# STM32F207VC_Mini.net
KiCad netlist of a schematic drawn in Altium Designer
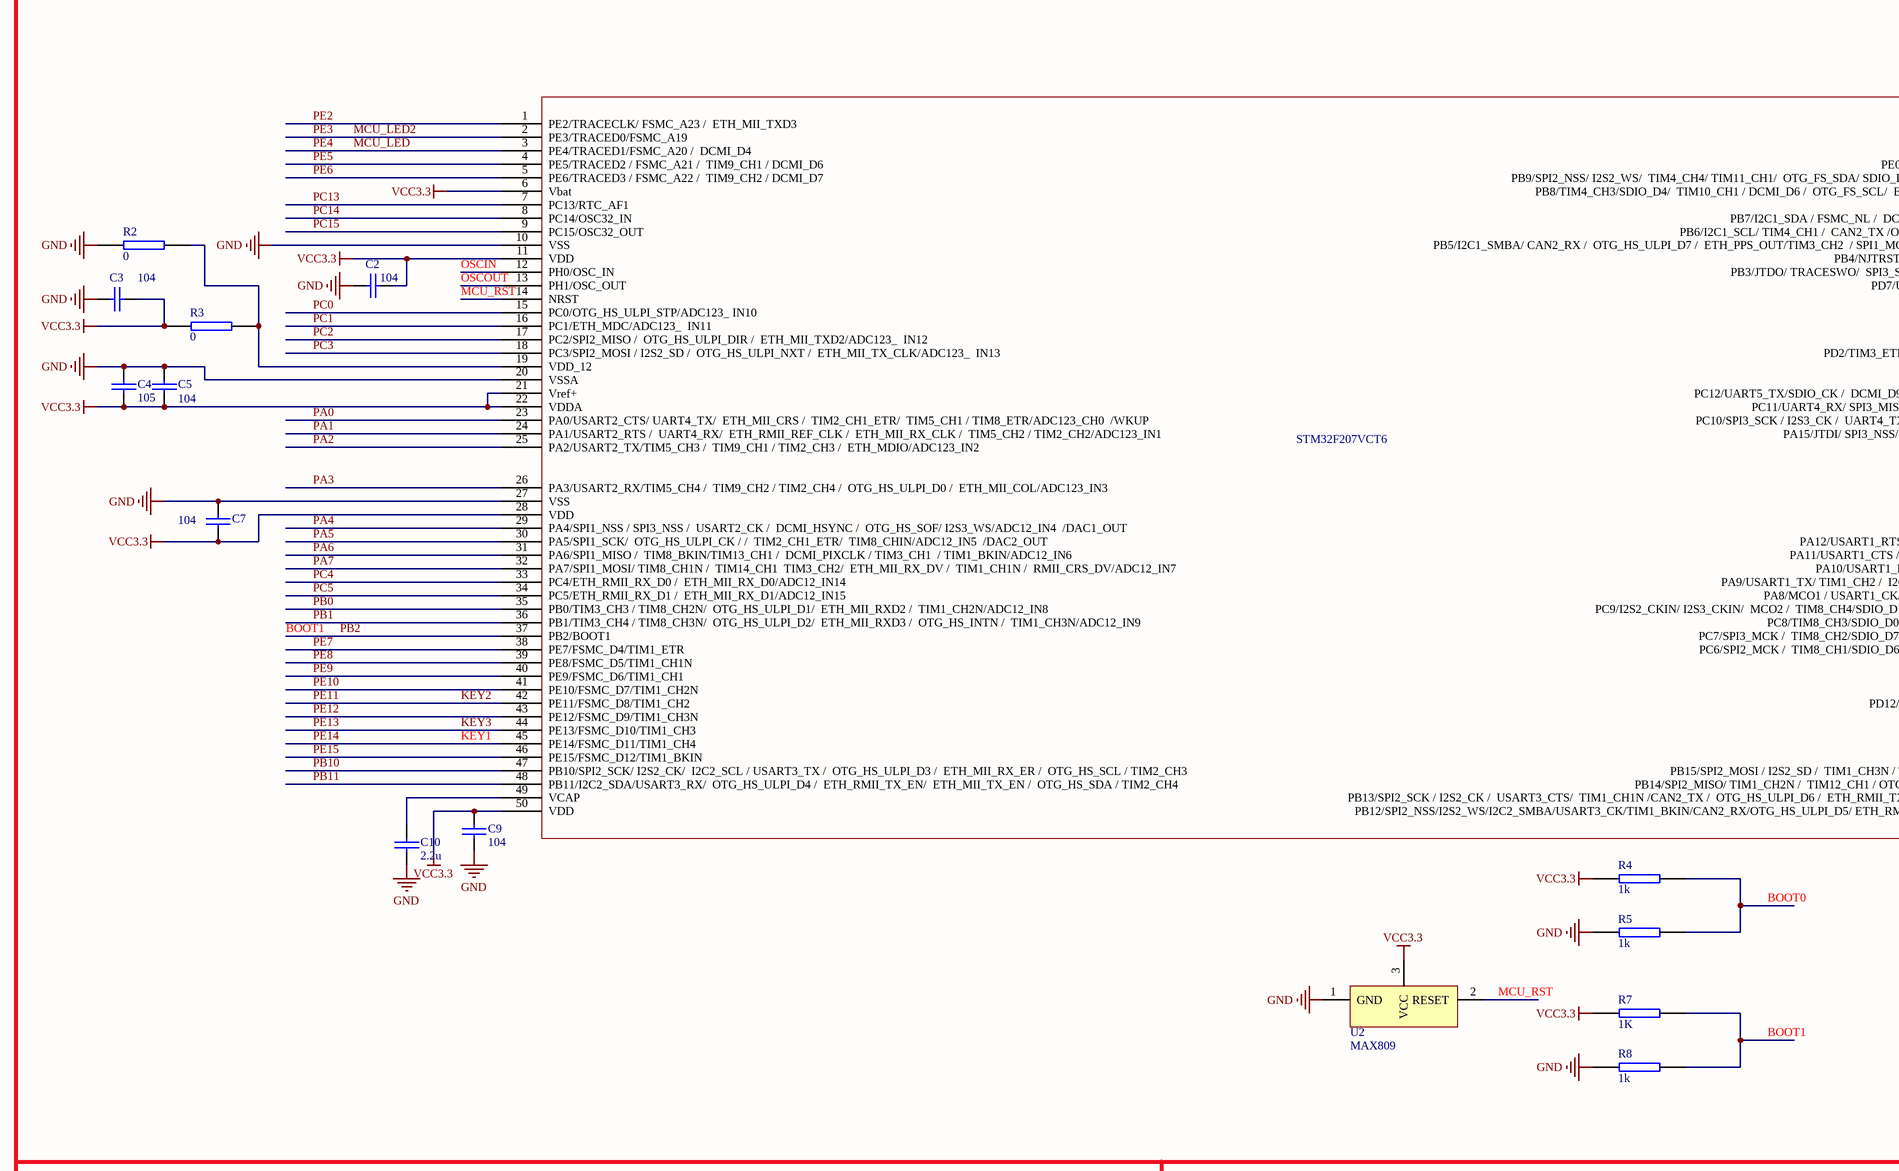
[diagram p0: STM32F207VC_Mini.SchDoc, top left]
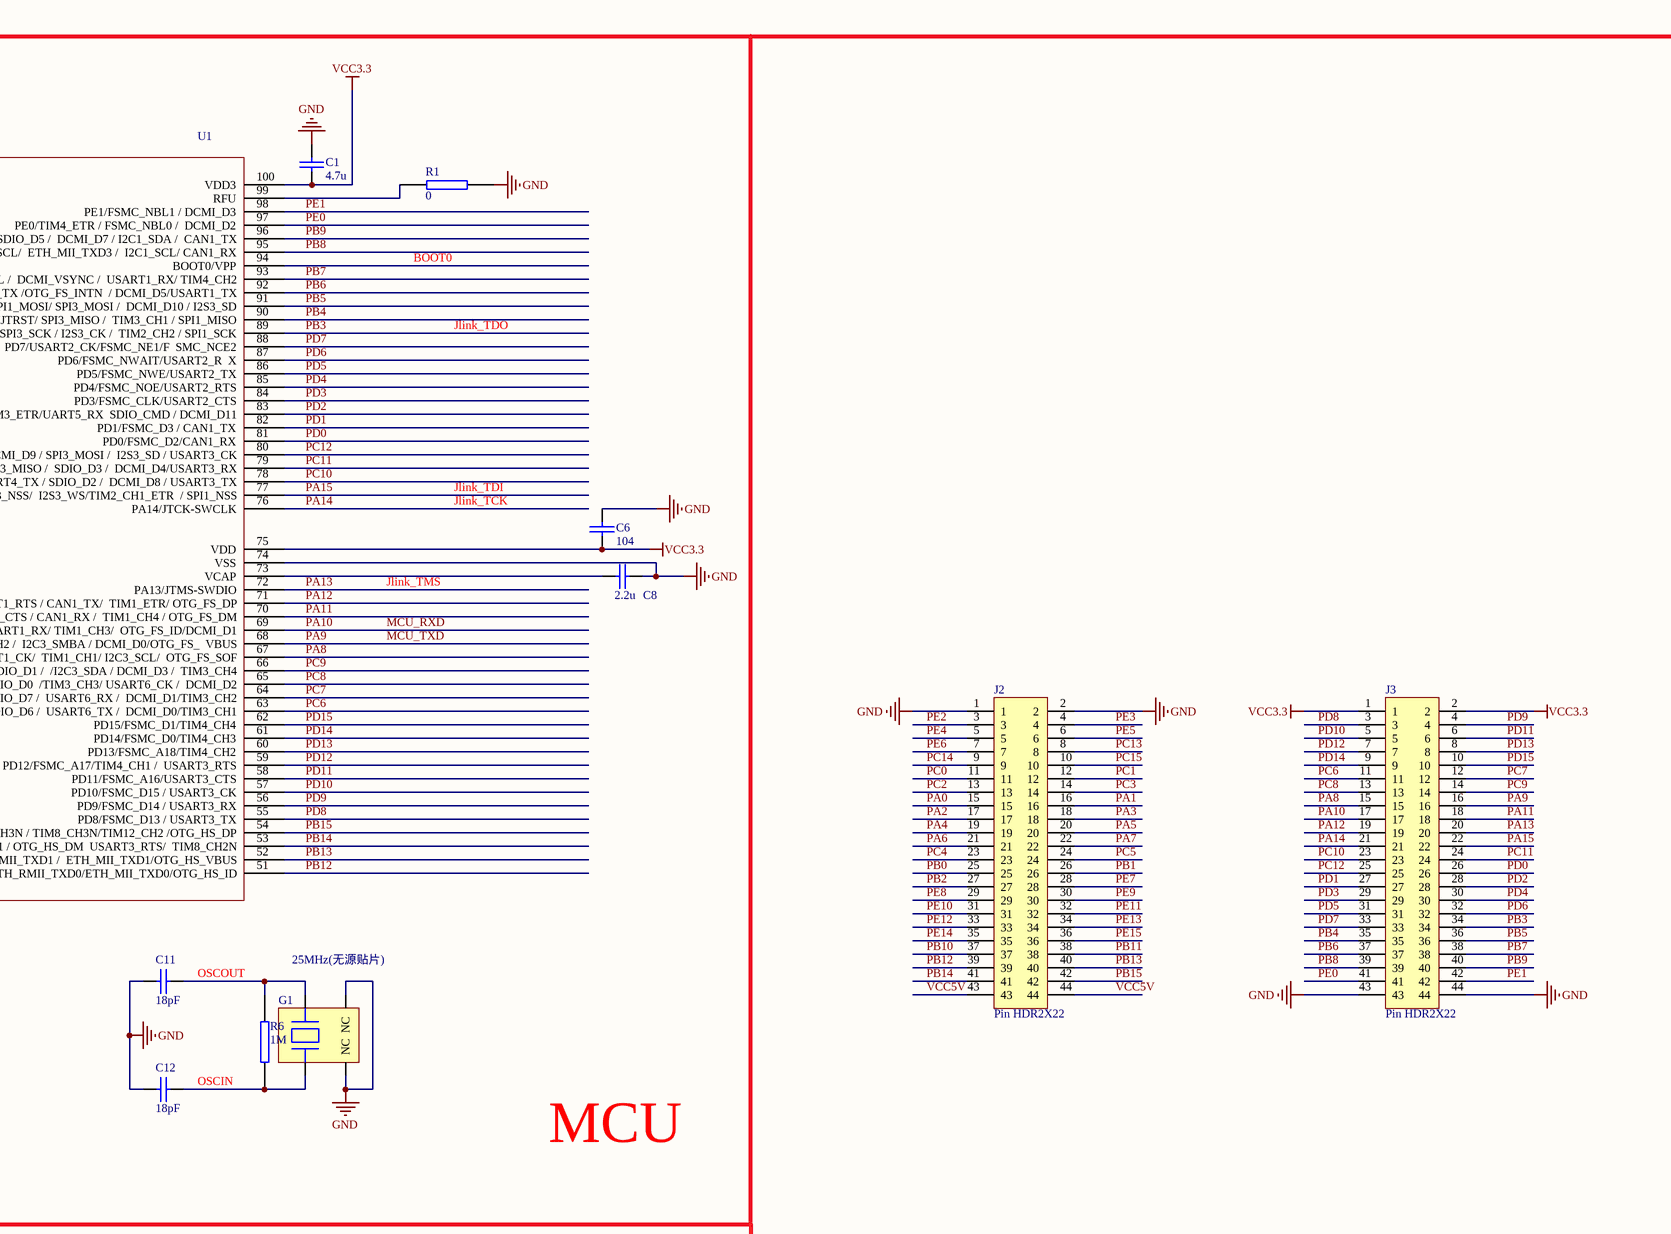
[diagram p1: STM32F207VC_Mini.SchDoc, top middle]
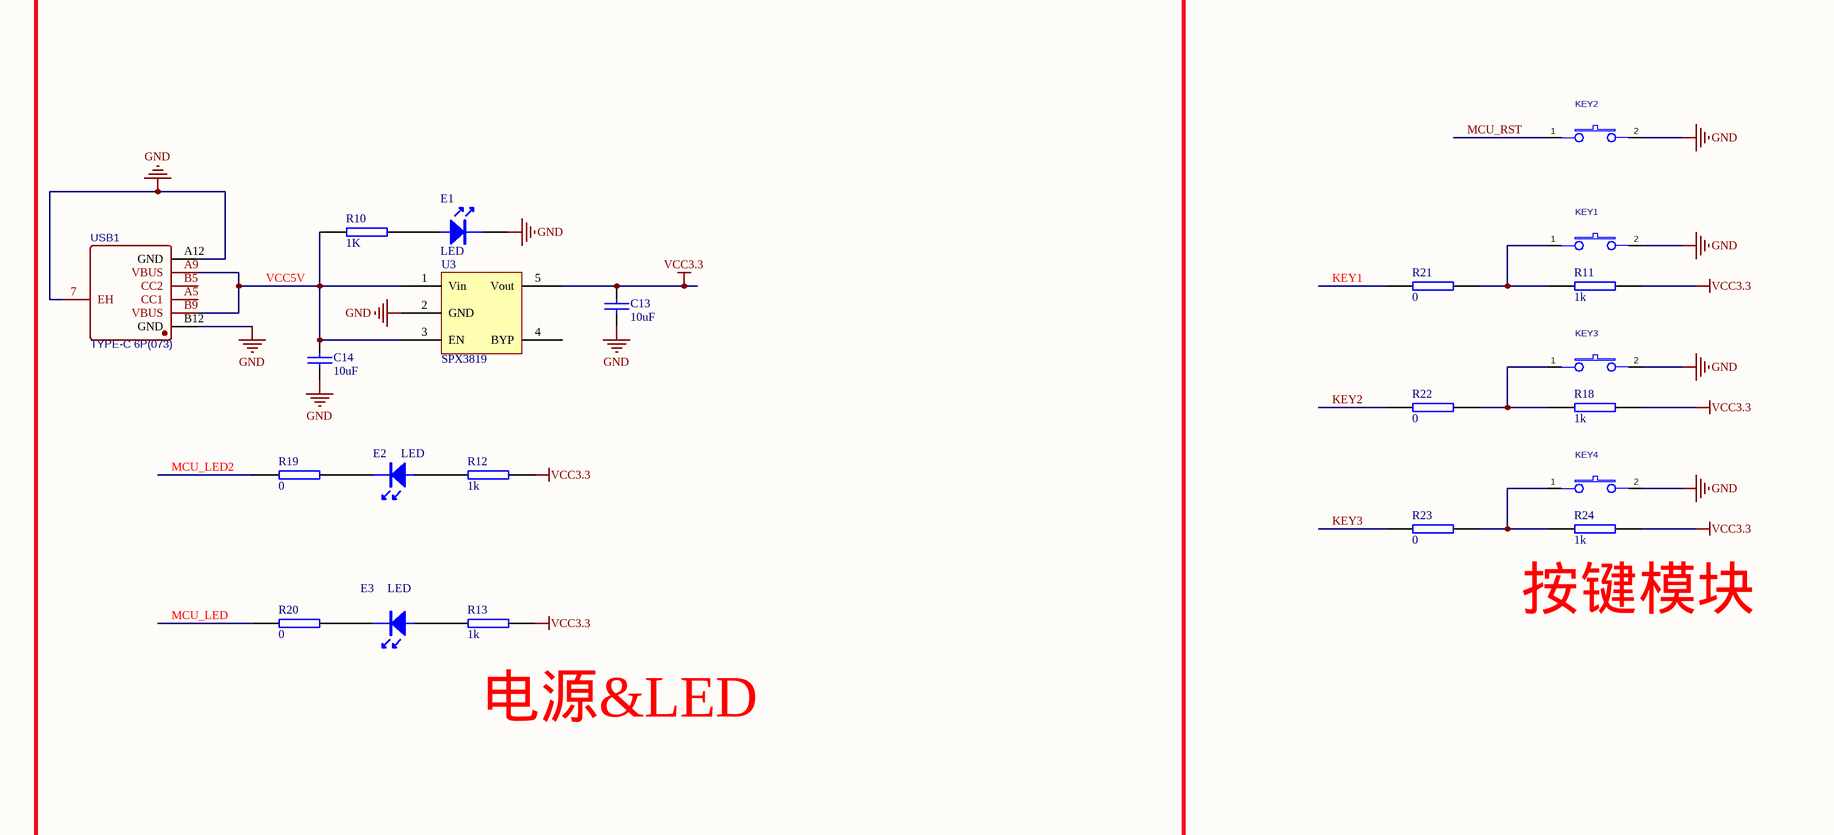
[diagram p2: STM32F207VC_Mini.SchDoc, bottom left]
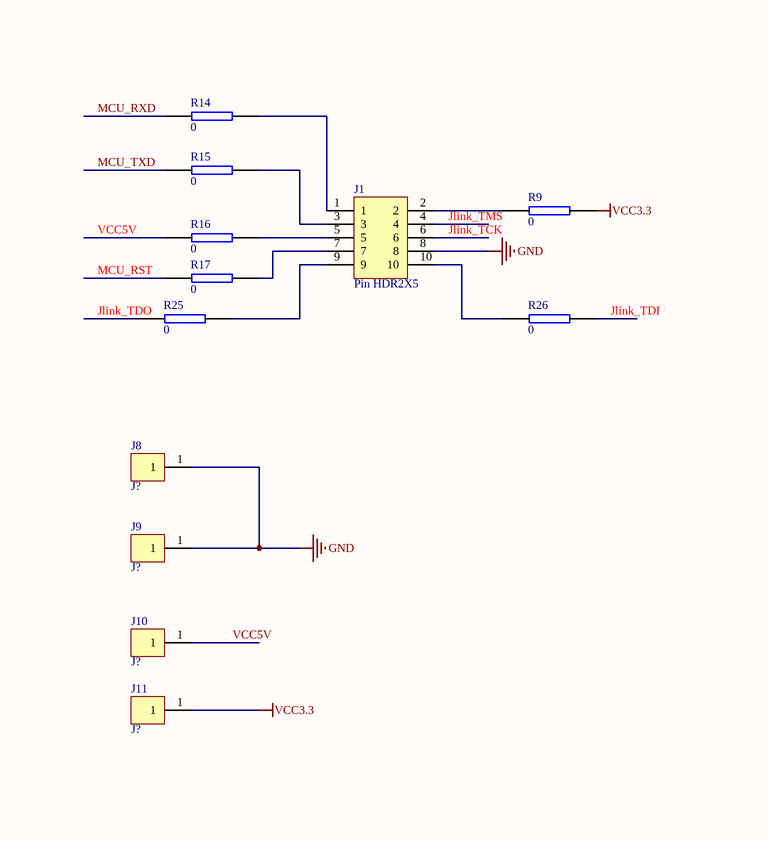
[diagram p3: STM32F207VC_Mini.SchDoc, bottom middle]

(export (version "E")
  (design (tool "Eeschema 10.0.6"))
  (components
    (comp (ref "C1")
      (value "4.7u")
      (footprint "0603")
      (description "贴片电容")
      (libsource (lib "ZXBC") (part "CAP Nonpolarity"))
    )
    (comp (ref "C2")
      (value "104")
      (footprint "0603")
      (description "贴片电容")
      (libsource (lib "ZXBC") (part "CAP Nonpolarity"))
    )
    (comp (ref "C3")
      (value "104")
      (footprint "0603")
      (description "贴片电容")
      (libsource (lib "ZXBC") (part "CAP Nonpolarity"))
    )
    (comp (ref "C4")
      (value "105")
      (footprint "0603")
      (description "贴片电容")
      (libsource (lib "ZXBC") (part "CAP Nonpolarity"))
    )
    (comp (ref "C5")
      (value "104")
      (footprint "0603")
      (description "贴片电容")
      (libsource (lib "ZXBC") (part "CAP Nonpolarity"))
    )
    (comp (ref "C6")
      (value "104")
      (footprint "0603")
      (description "贴片电容")
      (libsource (lib "ZXBC") (part "CAP Nonpolarity"))
    )
    (comp (ref "C7")
      (value "104")
      (footprint "0603")
      (description "贴片电容")
      (libsource (lib "ZXBC") (part "CAP Nonpolarity"))
    )
    (comp (ref "C8")
      (value "2.2u")
      (footprint "0603")
      (description "贴片电容")
      (libsource (lib "ZXBC") (part "CAP Nonpolarity"))
    )
    (comp (ref "C9")
      (value "104")
      (footprint "0603")
      (description "贴片电容")
      (libsource (lib "ZXBC") (part "CAP Nonpolarity"))
    )
    (comp (ref "C10")
      (value "2.2u")
      (footprint "0603")
      (description "贴片电容")
      (libsource (lib "ZXBC") (part "CAP Nonpolarity"))
    )
    (comp (ref "C11")
      (value "18pF")
      (footprint "0603")
      (description "无极电容")
      (libsource (lib "ZXBC") (part "CAP Nonpolarity"))
    )
    (comp (ref "C12")
      (value "18pF")
      (footprint "0603")
      (description "无极电容")
      (libsource (lib "ZXBC") (part "CAP Nonpolarity"))
    )
    (comp (ref "C13")
      (value "10uF")
      (footprint "0603")
      (description "无极电容")
      (libsource (lib "ZXBC") (part "CAP Nonpolarity"))
    )
    (comp (ref "C14")
      (value "10uF")
      (footprint "0603")
      (description "无极电容")
      (libsource (lib "ZXBC") (part "CAP Nonpolarity"))
    )
    (comp (ref "E1")
      (value "LED")
      (footprint "LED_0603L")
      (description "LED灯")
      (libsource (lib "ZXBC") (part "LED"))
    )
    (comp (ref "E2")
      (value "LED")
      (footprint "LED_0603L")
      (description "LED灯")
      (libsource (lib "ZXBC") (part "LED"))
    )
    (comp (ref "E3")
      (value "LED")
      (footprint "LED_0603L")
      (description "LED灯")
      (libsource (lib "ZXBC") (part "LED"))
    )
    (comp (ref "G1")
      (value "25MHz(无源贴片)")
      (footprint "G3225")
      (description "无源晶振MCU使用")
      (libsource (lib "ZXBC") (part "MM-11B"))
    )
    (comp (ref "J1")
      (value "Pin HDR2X5")
      (footprint "Pin HDR2X5/2.54mm-S")
      (libsource (lib "排针") (part "Pin HDR2X5"))
    )
    (comp (ref "J2")
      (value "Pin HDR2X22")
      (footprint "Pin HDR2X22/2.54mm-W")
      (libsource (lib "排针") (part "Pin HDR2X22"))
    )
    (comp (ref "J3")
      (value "Pin HDR2X22")
      (footprint "Pin HDR2X22/2.54mm-W")
      (libsource (lib "排针") (part "Pin HDR2X22"))
    )
    (comp (ref "J8")
      (value "J?")
      (footprint "固定柱")
      (description "固定柱")
      (libsource (lib "chenjd") (part "固定柱"))
    )
    (comp (ref "J9")
      (value "J?")
      (footprint "固定柱")
      (description "固定柱")
      (libsource (lib "chenjd") (part "固定柱"))
    )
    (comp (ref "J10")
      (value "J?")
      (footprint "固定柱")
      (description "固定柱")
      (libsource (lib "chenjd") (part "固定柱"))
    )
    (comp (ref "J11")
      (value "J?")
      (footprint "固定柱")
      (description "固定柱")
      (libsource (lib "chenjd") (part "固定柱"))
    )
    (comp (ref "KEY1")
      (value "H-3650AADW(NC)")
      (footprint "SW_PB_2P")
      (description "贴片按钮-2PIN(NC)")
      (fields (field (name "MANUFACTURER") "?"))
      (libsource (lib "chenjd") (part "SW_PB_2P"))
    )
    (comp (ref "KEY2")
      (value "H-3650AADW(NC)")
      (footprint "SW_PB_2P")
      (description "贴片按钮-2PIN(NC)")
      (fields (field (name "MANUFACTURER") "?"))
      (libsource (lib "") (part "SW_PB_2P_1"))
    )
    (comp (ref "KEY3")
      (value "H-3650AADW(NC)")
      (footprint "SW_PB_2P")
      (description "贴片按钮-2PIN(NC)")
      (fields (field (name "MANUFACTURER") "?"))
      (libsource (lib "chenjd") (part "SW_PB_2P"))
    )
    (comp (ref "KEY4")
      (value "H-3650AADW(NC)")
      (footprint "SW_PB_2P")
      (description "贴片按钮-2PIN(NC)")
      (fields (field (name "MANUFACTURER") "?"))
      (libsource (lib "chenjd") (part "SW_PB_2P"))
    )
    (comp (ref "R1") (value "0") (footprint "0603") (description "电阻") (libsource (lib "ZXBC") (part "R")))
    (comp (ref "R2") (value "0") (footprint "0603") (description "电阻") (libsource (lib "ZXBC") (part "R")))
    (comp (ref "R3") (value "0") (footprint "0603") (description "电阻") (libsource (lib "ZXBC") (part "R")))
    (comp (ref "R4") (value "1k") (footprint "0603") (description "电阻") (libsource (lib "ZXBC") (part "R")))
    (comp (ref "R5") (value "1k") (footprint "0603") (description "电阻") (libsource (lib "ZXBC") (part "R")))
    (comp (ref "R6") (value "1M") (footprint "0603") (description "电阻") (libsource (lib "ZXBC") (part "R")))
    (comp (ref "R7") (value "1K") (footprint "0603") (description "电阻") (libsource (lib "ZXBC") (part "R")))
    (comp (ref "R8") (value "1k") (footprint "0603") (description "电阻") (libsource (lib "ZXBC") (part "R")))
    (comp (ref "R9") (value "0") (footprint "0603") (description "电阻") (libsource (lib "chenjd") (part "R")))
    (comp (ref "R10") (value "1K") (footprint "0603") (description "电阻") (libsource (lib "ZXBC") (part "R")))
    (comp (ref "R11") (value "1k") (footprint "0603") (description "电阻") (libsource (lib "ZXBC") (part "R")))
    (comp (ref "R12") (value "1k") (footprint "0603") (description "电阻") (libsource (lib "ZXBC") (part "R")))
    (comp (ref "R13") (value "1k") (footprint "0603") (description "电阻") (libsource (lib "ZXBC") (part "R")))
    (comp (ref "R14") (value "0") (footprint "0603") (description "电阻") (libsource (lib "chenjd") (part "R")))
    (comp (ref "R15") (value "0") (footprint "0603") (description "电阻") (libsource (lib "chenjd") (part "R")))
    (comp (ref "R16") (value "0") (footprint "0603") (description "电阻") (libsource (lib "chenjd") (part "R")))
    (comp (ref "R17") (value "0") (footprint "0603") (description "电阻") (libsource (lib "chenjd") (part "R")))
    (comp (ref "R18") (value "1k") (footprint "0603") (description "电阻") (libsource (lib "ZXBC") (part "R")))
    (comp (ref "R19") (value "0") (footprint "0603") (description "电阻") (libsource (lib "chenjd") (part "R")))
    (comp (ref "R20") (value "0") (footprint "0603") (description "电阻") (libsource (lib "chenjd") (part "R")))
    (comp (ref "R21") (value "0") (footprint "0603") (description "电阻") (libsource (lib "chenjd") (part "R")))
    (comp (ref "R22") (value "0") (footprint "0603") (description "电阻") (libsource (lib "chenjd") (part "R")))
    (comp (ref "R23") (value "0") (footprint "0603") (description "电阻") (libsource (lib "chenjd") (part "R")))
    (comp (ref "R24") (value "1k") (footprint "0603") (description "电阻") (libsource (lib "ZXBC") (part "R")))
    (comp (ref "R25") (value "0") (footprint "0603") (description "电阻") (libsource (lib "chenjd") (part "R")))
    (comp (ref "R26") (value "0") (footprint "0603") (description "电阻") (libsource (lib "chenjd") (part "R")))
    (comp (ref "U1")
      (value "STM32F207VCT6")
      (footprint "LQFP-100")
      (libsource (lib "ZXBC") (part "STM32F207-1"))
    )
    (comp (ref "U2")
      (value "MAX809")
      (footprint "SOT32-809")
      (description "复位IC")
      (libsource (lib "ZXBC") (part "MAX809"))
    )
    (comp (ref "U3")
      (value "SPX3819")
      (footprint "SOT-23-5")
      (description "稳压器")
      (libsource (lib "ZXBC") (part "SPX3819"))
    )
    (comp (ref "USB1")
      (value "TYPE-C 6P(073)")
      (footprint "USB-C-6P")
      (description "6脚usb type-c接口")
      (fields (field (name "BOM_SUPPLIER PART") "C668623") (field (name "CONTRIBUTOR") "LCSC"))
      (libsource (lib "chenjd") (part "USB-TYPE-C 6P"))
    )
  )
  (nets
    (net (code "1") (name "/BOOT0") (class "Default")
      (node (ref "R4") (pin "2") (pinfunction "2_2") (pintype "passive"))
      (node (ref "R5") (pin "2") (pinfunction "2_2") (pintype "passive"))
      (node (ref "U1") (pin "94") (pinfunction "BOOT0/VPP_94") (pintype "passive"))
    )
    (net (code "2") (name "/BOOT1") (class "Default")
      (node (ref "J2") (pin "27") (pinfunction "27_27") (pintype "passive"))
      (node (ref "R7") (pin "2") (pinfunction "2_2") (pintype "passive"))
      (node (ref "R8") (pin "2") (pinfunction "2_2") (pintype "passive"))
      (node (ref "U1") (pin "37") (pinfunction "PB2/BOOT1_37") (pintype "passive"))
    )
    (net (code "3") (name "/Jlink_TCK") (class "Default")
      (node (ref "J1") (pin "6") (pinfunction "6_6") (pintype "passive"))
      (node (ref "J3") (pin "21") (pinfunction "21_21") (pintype "passive"))
      (node (ref "U1") (pin "76") (pinfunction "PA14/JTCK-SWCLK_76") (pintype "passive"))
    )
    (net (code "4") (name "/Jlink_TDI") (class "Default")
      (node (ref "J3") (pin "22") (pinfunction "22_22") (pintype "passive"))
      (node (ref "R26") (pin "2") (pinfunction "2_2") (pintype "passive"))
      (node (ref "U1") (pin "77") (pinfunction "PA15/JTDI/_SPI3_NSS/__I2S3_WS/TIM2_CH1_ETR__/_SPI1_NSS_77") (pintype "passive"))
    )
    (net (code "5") (name "/Jlink_TDO") (class "Default")
      (node (ref "J3") (pin "34") (pinfunction "34_34") (pintype "passive"))
      (node (ref "R25") (pin "1") (pinfunction "1_1") (pintype "passive"))
      (node (ref "U1") (pin "89") (pinfunction "PB3/JTDO/_TRACESWO/__SPI3_SCK_/_I2S3_CK_/__TIM2_CH2_/_SPI1_SCK_89") (pintype "passive"))
    )
    (net (code "6") (name "/Jlink_TMS") (class "Default")
      (node (ref "J1") (pin "4") (pinfunction "4_4") (pintype "passive"))
      (node (ref "J3") (pin "20") (pinfunction "20_20") (pintype "passive"))
      (node (ref "U1") (pin "72") (pinfunction "PA13/JTMS-SWDIO_72") (pintype "passive"))
    )
    (net (code "7") (name "/KEY1") (class "Default")
      (node (ref "J2") (pin "35") (pinfunction "35_35") (pintype "passive"))
      (node (ref "R21") (pin "1") (pinfunction "1_1") (pintype "passive"))
      (node (ref "U1") (pin "45") (pinfunction "PE14/FSMC_D11/TIM1_CH4_45") (pintype "passive"))
    )
    (net (code "8") (name "/KEY2") (class "Default")
      (node (ref "J2") (pin "32") (pinfunction "32_32") (pintype "passive"))
      (node (ref "R22") (pin "1") (pinfunction "1_1") (pintype "passive"))
      (node (ref "U1") (pin "42") (pinfunction "PE11/FSMC_D8/TIM1_CH2_42") (pintype "passive"))
    )
    (net (code "9") (name "/KEY3") (class "Default")
      (node (ref "J2") (pin "34") (pinfunction "34_34") (pintype "passive"))
      (node (ref "R23") (pin "1") (pinfunction "1_1") (pintype "passive"))
      (node (ref "U1") (pin "44") (pinfunction "PE13/FSMC_D10/TIM1_CH3_44") (pintype "passive"))
    )
    (net (code "10") (name "/MCU_LED") (class "Default")
      (node (ref "J2") (pin "5") (pinfunction "5_5") (pintype "passive"))
      (node (ref "R20") (pin "1") (pinfunction "1_1") (pintype "passive"))
      (node (ref "U1") (pin "3") (pinfunction "PE4/TRACED1/FSMC_A20_/__DCMI_D4_3") (pintype "passive"))
    )
    (net (code "11") (name "/MCU_LED2") (class "Default")
      (node (ref "J2") (pin "4") (pinfunction "4_4") (pintype "passive"))
      (node (ref "R19") (pin "1") (pinfunction "1_1") (pintype "passive"))
      (node (ref "U1") (pin "2") (pinfunction "PE3/TRACED0/FSMC_A19_2") (pintype "passive"))
    )
    (net (code "12") (name "/MCU_RST") (class "Default")
      (node (ref "KEY2") (pin "1") (pinfunction "1_1") (pintype "passive"))
      (node (ref "R17") (pin "1") (pinfunction "1_1") (pintype "passive"))
      (node (ref "U1") (pin "14") (pinfunction "NRST_14") (pintype "passive"))
      (node (ref "U2") (pin "2") (pinfunction "RESET_2") (pintype "passive"))
    )
    (net (code "13") (name "/MCU_RXD") (class "Default")
      (node (ref "J3") (pin "17") (pinfunction "17_17") (pintype "passive"))
      (node (ref "R14") (pin "1") (pinfunction "1_1") (pintype "passive"))
      (node (ref "U1") (pin "69") (pinfunction "PA10/USART1_RX/_TIM1_CH3/__OTG_FS_ID/DCMI_D1_69") (pintype "passive"))
    )
    (net (code "14") (name "/MCU_TXD") (class "Default")
      (node (ref "J3") (pin "16") (pinfunction "16_16") (pintype "passive"))
      (node (ref "R15") (pin "1") (pinfunction "1_1") (pintype "passive"))
      (node (ref "U1") (pin "68") (pinfunction "PA9/USART1_TX/_TIM1_CH2_/__I2C3_SMBA_/_DCMI_D0/OTG_FS___VBUS_68") (pintype "passive"))
    )
    (net (code "15") (name "/OSCIN") (class "Default")
      (node (ref "C12") (pin "2") (pintype "passive"))
      (node (ref "G1") (pin "1") (pinfunction "1_1") (pintype "passive"))
      (node (ref "R6") (pin "2") (pinfunction "2_2") (pintype "passive"))
      (node (ref "U1") (pin "12") (pinfunction "PH0/OSC_IN_12") (pintype "passive"))
    )
    (net (code "16") (name "/OSCOUT") (class "Default")
      (node (ref "C11") (pin "2") (pintype "passive"))
      (node (ref "G1") (pin "3") (pinfunction "3_3") (pintype "passive"))
      (node (ref "R6") (pin "1") (pinfunction "1_1") (pintype "passive"))
      (node (ref "U1") (pin "13") (pinfunction "PH1/OSC_OUT_13") (pintype "passive"))
    )
    (net (code "17") (name "/PA0") (class "Default")
      (node (ref "J2") (pin "15") (pinfunction "15_15") (pintype "passive"))
      (node (ref "U1") (pin "23") (pinfunction "PA0/USART2_CTS/_UART4_TX/__ETH_MII_CRS_/__TIM2_CH1_ETR/__TIM5_CH1_/_TIM8_ETR/ADC123_CH0__/WKUP_23") (pintype "passive"))
    )
    (net (code "18") (name "/PA1") (class "Default")
      (node (ref "J2") (pin "16") (pinfunction "16_16") (pintype "passive"))
      (node (ref "U1") (pin "24") (pinfunction "PA1/USART2_RTS_/__UART4_RX/__ETH_RMII_REF_CLK_/__ETH_MII_RX_CLK_/__TIM5_CH2_/_TIM2_CH2/ADC123_IN1_24") (pintype "passive"))
    )
    (net (code "19") (name "/PA2") (class "Default")
      (node (ref "J2") (pin "17") (pinfunction "17_17") (pintype "passive"))
      (node (ref "U1") (pin "25") (pinfunction "PA2/USART2_TX/TIM5_CH3_/__TIM9_CH1_/_TIM2_CH3_/__ETH_MDIO/ADC123_IN2_25") (pintype "passive"))
    )
    (net (code "20") (name "/PA3") (class "Default")
      (node (ref "J2") (pin "18") (pinfunction "18_18") (pintype "passive"))
      (node (ref "U1") (pin "26") (pinfunction "PA3/USART2_RX/TIM5_CH4_/__TIM9_CH2_/_TIM2_CH4_/__OTG_HS_ULPI_D0_/__ETH_MII_COL/ADC123_IN3_26") (pintype "passive"))
    )
    (net (code "21") (name "/PA4") (class "Default")
      (node (ref "J2") (pin "19") (pinfunction "19_19") (pintype "passive"))
      (node (ref "U1") (pin "29") (pinfunction "PA4/SPI1_NSS_/_SPI3_NSS_/__USART2_CK_/__DCMI_HSYNC_/__OTG_HS_SOF/_I2S3_WS/ADC12_IN4__/DAC1_OUT_29") (pintype "passive"))
    )
    (net (code "22") (name "/PA5") (class "Default")
      (node (ref "J2") (pin "20") (pinfunction "20_20") (pintype "passive"))
      (node (ref "U1") (pin "30") (pinfunction "PA5/SPI1_SCK/__OTG_HS_ULPI_CK_/_/__TIM2_CH1_ETR/__TIM8_CHIN/ADC12_IN5__/DAC2_OUT_30") (pintype "passive"))
    )
    (net (code "23") (name "/PA6") (class "Default")
      (node (ref "J2") (pin "21") (pinfunction "21_21") (pintype "passive"))
      (node (ref "U1") (pin "31") (pinfunction "PA6/SPI1_MISO_/__TIM8_BKIN/TIM13_CH1_/__DCMI_PIXCLK_/_TIM3_CH1__/_TIM1_BKIN/ADC12_IN6_31") (pintype "passive"))
    )
    (net (code "24") (name "/PA7") (class "Default")
      (node (ref "J2") (pin "22") (pinfunction "22_22") (pintype "passive"))
      (node (ref "U1") (pin "32") (pinfunction "PA7/SPI1_MOSI/_TIM8_CH1N_/__TIM14_CH1__TIM3_CH2/__ETH_MII_RX_DV_/__TIM1_CH1N_/__RMII_CRS_DV/ADC12_IN7_32") (pintype "passive"))
    )
    (net (code "25") (name "/PA8") (class "Default")
      (node (ref "J3") (pin "15") (pinfunction "15_15") (pintype "passive"))
      (node (ref "U1") (pin "67") (pinfunction "PA8/MCO1_/_USART1_CK/__TIM1_CH1/_I2C3_SCL/__OTG_FS_SOF_67") (pintype "passive"))
    )
    (net (code "26") (name "/PA11") (class "Default")
      (node (ref "J3") (pin "18") (pinfunction "18_18") (pintype "passive"))
      (node (ref "U1") (pin "70") (pinfunction "PA11/USART1_CTS_/_CAN1_RX_/__TIM1_CH4_/_OTG_FS_DM_70") (pintype "passive"))
    )
    (net (code "27") (name "/PA12") (class "Default")
      (node (ref "J3") (pin "19") (pinfunction "19_19") (pintype "passive"))
      (node (ref "U1") (pin "71") (pinfunction "PA12/USART1_RTS_/_CAN1_TX/__TIM1_ETR/_OTG_FS_DP_71") (pintype "passive"))
    )
    (net (code "28") (name "/PB0") (class "Default")
      (node (ref "J2") (pin "25") (pinfunction "25_25") (pintype "passive"))
      (node (ref "U1") (pin "35") (pinfunction "PB0/TIM3_CH3_/_TIM8_CH2N/__OTG_HS_ULPI_D1/__ETH_MII_RXD2_/__TIM1_CH2N/ADC12_IN8_35") (pintype "passive"))
    )
    (net (code "29") (name "/PB1") (class "Default")
      (node (ref "J2") (pin "26") (pinfunction "26_26") (pintype "passive"))
      (node (ref "U1") (pin "36") (pinfunction "PB1/TIM3_CH4_/_TIM8_CH3N/__OTG_HS_ULPI_D2/__ETH_MII_RXD3_/__OTG_HS_INTN_/__TIM1_CH3N/ADC12_IN9_36") (pintype "passive"))
    )
    (net (code "30") (name "/PB4") (class "Default")
      (node (ref "J3") (pin "35") (pinfunction "35_35") (pintype "passive"))
      (node (ref "U1") (pin "90") (pinfunction "PB4/NJTRST/_SPI3_MISO_/__TIM3_CH1_/_SPI1_MISO_90") (pintype "passive"))
    )
    (net (code "31") (name "/PB5") (class "Default")
      (node (ref "J3") (pin "36") (pinfunction "36_36") (pintype "passive"))
      (node (ref "U1") (pin "91") (pinfunction "PB5/I2C1_SMBA/_CAN2_RX_/__OTG_HS_ULPI_D7_/__ETH_PPS_OUT/TIM3_CH2__/_SPI1_MOSI/_SPI3_MOSI_/__DCMI_D10_/_I2S3_SD_91") (pintype "passive"))
    )
    (net (code "32") (name "/PB6") (class "Default")
      (node (ref "J3") (pin "37") (pinfunction "37_37") (pintype "passive"))
      (node (ref "U1") (pin "92") (pinfunction "PB6/I2C1_SCL/_TIM4_CH1_/__CAN2_TX_/OTG_FS_INTN__/_DCMI_D5/USART1_TX_92") (pintype "passive"))
    )
    (net (code "33") (name "/PB7") (class "Default")
      (node (ref "J3") (pin "38") (pinfunction "38_38") (pintype "passive"))
      (node (ref "U1") (pin "93") (pinfunction "PB7/I2C1_SDA_/_FSMC_NL_/__DCMI_VSYNC_/__USART1_RX/_TIM4_CH2_93") (pintype "passive"))
    )
    (net (code "34") (name "/PB8") (class "Default")
      (node (ref "J3") (pin "39") (pinfunction "39_39") (pintype "passive"))
      (node (ref "U1") (pin "95") (pinfunction "PB8/TIM4_CH3/SDIO_D4/__TIM10_CH1_/_DCMI_D6_/__OTG_FS_SCL/__ETH_MII_TXD3_/__I2C1_SCL/_CAN1_RX_95") (pintype "passive"))
    )
    (net (code "35") (name "/PB9") (class "Default")
      (node (ref "J3") (pin "40") (pinfunction "40_40") (pintype "passive"))
      (node (ref "U1") (pin "96") (pinfunction "PB9/SPI2_NSS/_I2S2_WS/__TIM4_CH4/_TIM11_CH1/__OTG_FS_SDA/_SDIO_D5_/__DCMI_D7_/_I2C1_SDA_/__CAN1_TX_96") (pintype "passive"))
    )
    (net (code "36") (name "/PB10") (class "Default")
      (node (ref "J2") (pin "37") (pinfunction "37_37") (pintype "passive"))
      (node (ref "U1") (pin "47") (pinfunction "PB10/SPI2_SCK/_I2S2_CK/__I2C2_SCL_/_USART3_TX_/__OTG_HS_ULPI_D3_/__ETH_MII_RX_ER_/__OTG_HS_SCL_/_TIM2_CH3_47") (pintype "passive"))
    )
    (net (code "37") (name "/PB11") (class "Default")
      (node (ref "J2") (pin "38") (pinfunction "38_38") (pintype "passive"))
      (node (ref "U1") (pin "48") (pinfunction "PB11/I2C2_SDA/USART3_RX/__OTG_HS_ULPI_D4_/__ETH_RMII_TX_EN/__ETH_MII_TX_EN_/__OTG_HS_SDA_/_TIM2_CH4_48") (pintype "passive"))
    )
    (net (code "38") (name "/PB12") (class "Default")
      (node (ref "J2") (pin "39") (pinfunction "39_39") (pintype "passive"))
      (node (ref "U1") (pin "51") (pinfunction "PB12/SPI2_NSS/I2S2_WS/I2C2_SMBA/USART3_CK/TIM1_BKIN/CAN2_RX/OTG_HS_ULPI_D5/_ETH_RMII_TXD0/ETH_MII_TXD0/OTG_HS_ID_51") (pintype "passive"))
    )
    (net (code "39") (name "/PB13") (class "Default")
      (node (ref "J2") (pin "40") (pinfunction "40_40") (pintype "passive"))
      (node (ref "U1") (pin "52") (pinfunction "PB13/SPI2_SCK_/_I2S2_CK_/__USART3_CTS/__TIM1_CH1N_/CAN2_TX_/__OTG_HS_ULPI_D6_/__ETH_RMII_TXD1_/__ETH_MII_TXD1/OTG_HS_VBUS_52") (pintype "passive"))
    )
    (net (code "40") (name "/PB14") (class "Default")
      (node (ref "J2") (pin "41") (pinfunction "41_41") (pintype "passive"))
      (node (ref "U1") (pin "53") (pinfunction "PB14/SPI2_MISO/_TIM1_CH2N_/__TIM12_CH1_/_OTG_HS_DM__USART3_RTS/__TIM8_CH2N_53") (pintype "passive"))
    )
    (net (code "41") (name "/PB15") (class "Default")
      (node (ref "J2") (pin "42") (pinfunction "42_42") (pintype "passive"))
      (node (ref "U1") (pin "54") (pinfunction "PB15/SPI2_MOSI_/_I2S2_SD_/__TIM1_CH3N_/_TIM8_CH3N/TIM12_CH2_/OTG_HS_DP_54") (pintype "passive"))
    )
    (net (code "42") (name "/PC0") (class "Default")
      (node (ref "J2") (pin "11") (pinfunction "11_11") (pintype "passive"))
      (node (ref "U1") (pin "15") (pinfunction "PC0/OTG_HS_ULPI_STP/ADC123__IN10_15") (pintype "passive"))
    )
    (net (code "43") (name "/PC1") (class "Default")
      (node (ref "J2") (pin "12") (pinfunction "12_12") (pintype "passive"))
      (node (ref "U1") (pin "16") (pinfunction "PC1/ETH_MDC/ADC123___IN11_16") (pintype "passive"))
    )
    (net (code "44") (name "/PC2") (class "Default")
      (node (ref "J2") (pin "13") (pinfunction "13_13") (pintype "passive"))
      (node (ref "U1") (pin "17") (pinfunction "PC2/SPI2_MISO_/__OTG_HS_ULPI_DIR_/__ETH_MII_TXD2/ADC123___IN12_17") (pintype "passive"))
    )
    (net (code "45") (name "/PC3") (class "Default")
      (node (ref "J2") (pin "14") (pinfunction "14_14") (pintype "passive"))
      (node (ref "U1") (pin "18") (pinfunction "PC3/SPI2_MOSI_/_I2S2_SD_/__OTG_HS_ULPI_NXT_/__ETH_MII_TX_CLK/ADC123___IN13_18") (pintype "passive"))
    )
    (net (code "46") (name "/PC4") (class "Default")
      (node (ref "J2") (pin "23") (pinfunction "23_23") (pintype "passive"))
      (node (ref "U1") (pin "33") (pinfunction "PC4/ETH_RMII_RX_D0_/__ETH_MII_RX_D0/ADC12_IN14_33") (pintype "passive"))
    )
    (net (code "47") (name "/PC5") (class "Default")
      (node (ref "J2") (pin "24") (pinfunction "24_24") (pintype "passive"))
      (node (ref "U1") (pin "34") (pinfunction "PC5/ETH_RMII_RX_D1_/__ETH_MII_RX_D1/ADC12_IN15_34") (pintype "passive"))
    )
    (net (code "48") (name "/PC6") (class "Default")
      (node (ref "J3") (pin "11") (pinfunction "11_11") (pintype "passive"))
      (node (ref "U1") (pin "63") (pinfunction "PC6/SPI2_MCK_/__TIM8_CH1/SDIO_D6_/__USART6_TX_/__DCMI_D0/TIM3_CH1_63") (pintype "passive"))
    )
    (net (code "49") (name "/PC7") (class "Default")
      (node (ref "J3") (pin "12") (pinfunction "12_12") (pintype "passive"))
      (node (ref "U1") (pin "64") (pinfunction "PC7/SPI3_MCK_/__TIM8_CH2/SDIO_D7_/__USART6_RX_/__DCMI_D1/TIM3_CH2_64") (pintype "passive"))
    )
    (net (code "50") (name "/PC8") (class "Default")
      (node (ref "J3") (pin "13") (pinfunction "13_13") (pintype "passive"))
      (node (ref "U1") (pin "65") (pinfunction "PC8/TIM8_CH3/SDIO_D0__/TIM3_CH3/_USART6_CK_/__DCMI_D2_65") (pintype "passive"))
    )
    (net (code "51") (name "/PC9") (class "Default")
      (node (ref "J3") (pin "14") (pinfunction "14_14") (pintype "passive"))
      (node (ref "U1") (pin "66") (pinfunction "PC9/I2S2_CKIN/_I2S3_CKIN/__MCO2_/__TIM8_CH4/SDIO_D1_/__/I2C3_SDA_/_DCMI_D3_/__TIM3_CH4_66") (pintype "passive"))
    )
    (net (code "52") (name "/PC10") (class "Default")
      (node (ref "J3") (pin "23") (pinfunction "23_23") (pintype "passive"))
      (node (ref "U1") (pin "78") (pinfunction "PC10/SPI3_SCK_/_I2S3_CK_/__UART4_TX_/_SDIO_D2_/__DCMI_D8_/_USART3_TX_78") (pintype "passive"))
    )
    (net (code "53") (name "/PC11") (class "Default")
      (node (ref "J3") (pin "24") (pinfunction "24_24") (pintype "passive"))
      (node (ref "U1") (pin "79") (pinfunction "PC11/UART4_RX/_SPI3_MISO_/__SDIO_D3_/__DCMI_D4/USART3_RX_79") (pintype "passive"))
    )
    (net (code "54") (name "/PC12") (class "Default")
      (node (ref "J3") (pin "25") (pinfunction "25_25") (pintype "passive"))
      (node (ref "U1") (pin "80") (pinfunction "PC12/UART5_TX/SDIO_CK_/__DCMI_D9_/_SPI3_MOSI_/__I2S3_SD_/_USART3_CK_80") (pintype "passive"))
    )
    (net (code "55") (name "/PC13") (class "Default")
      (node (ref "J2") (pin "8") (pinfunction "8_8") (pintype "passive"))
      (node (ref "U1") (pin "7") (pinfunction "PC13/RTC_AF1_7") (pintype "passive"))
    )
    (net (code "56") (name "/PC14") (class "Default")
      (node (ref "J2") (pin "9") (pinfunction "9_9") (pintype "passive"))
      (node (ref "U1") (pin "8") (pinfunction "PC14/OSC32_IN_8") (pintype "passive"))
    )
    (net (code "57") (name "/PC15") (class "Default")
      (node (ref "J2") (pin "10") (pinfunction "10_10") (pintype "passive"))
      (node (ref "U1") (pin "9") (pinfunction "PC15/OSC32_OUT_9") (pintype "passive"))
    )
    (net (code "58") (name "/PD0") (class "Default")
      (node (ref "J3") (pin "26") (pinfunction "26_26") (pintype "passive"))
      (node (ref "U1") (pin "81") (pinfunction "PD0/FSMC_D2/CAN1_RX_81") (pintype "passive"))
    )
    (net (code "59") (name "/PD1") (class "Default")
      (node (ref "J3") (pin "27") (pinfunction "27_27") (pintype "passive"))
      (node (ref "U1") (pin "82") (pinfunction "PD1/FSMC_D3_/_CAN1_TX_82") (pintype "passive"))
    )
    (net (code "60") (name "/PD2") (class "Default")
      (node (ref "J3") (pin "28") (pinfunction "28_28") (pintype "passive"))
      (node (ref "U1") (pin "83") (pinfunction "PD2/TIM3_ETR/UART5_RX__SDIO_CMD_/_DCMI_D11_83") (pintype "passive"))
    )
    (net (code "61") (name "/PD3") (class "Default")
      (node (ref "J3") (pin "29") (pinfunction "29_29") (pintype "passive"))
      (node (ref "U1") (pin "84") (pinfunction "PD3/FSMC_CLK/USART2_CTS_84") (pintype "passive"))
    )
    (net (code "62") (name "/PD4") (class "Default")
      (node (ref "J3") (pin "30") (pinfunction "30_30") (pintype "passive"))
      (node (ref "U1") (pin "85") (pinfunction "PD4/FSMC_NOE/USART2_RTS_85") (pintype "passive"))
    )
    (net (code "63") (name "/PD5") (class "Default")
      (node (ref "J3") (pin "31") (pinfunction "31_31") (pintype "passive"))
      (node (ref "U1") (pin "86") (pinfunction "PD5/FSMC_NWE/USART2_TX_86") (pintype "passive"))
    )
    (net (code "64") (name "/PD6") (class "Default")
      (node (ref "J3") (pin "32") (pinfunction "32_32") (pintype "passive"))
      (node (ref "U1") (pin "87") (pinfunction "PD6/FSMC_NWAIT/USART2_R__X_87") (pintype "passive"))
    )
    (net (code "65") (name "/PD7") (class "Default")
      (node (ref "J3") (pin "33") (pinfunction "33_33") (pintype "passive"))
      (node (ref "U1") (pin "88") (pinfunction "PD7/USART2_CK/FSMC_NE1/F__SMC_NCE2_88") (pintype "passive"))
    )
    (net (code "66") (name "/PD8") (class "Default")
      (node (ref "J3") (pin "3") (pinfunction "3_3") (pintype "passive"))
      (node (ref "U1") (pin "55") (pinfunction "PD8/FSMC_D13_/_USART3_TX_55") (pintype "passive"))
    )
    (net (code "67") (name "/PD9") (class "Default")
      (node (ref "J3") (pin "4") (pinfunction "4_4") (pintype "passive"))
      (node (ref "U1") (pin "56") (pinfunction "PD9/FSMC_D14_/_USART3_RX_56") (pintype "passive"))
    )
    (net (code "68") (name "/PD10") (class "Default")
      (node (ref "J3") (pin "5") (pinfunction "5_5") (pintype "passive"))
      (node (ref "U1") (pin "57") (pinfunction "PD10/FSMC_D15_/_USART3_CK_57") (pintype "passive"))
    )
    (net (code "69") (name "/PD11") (class "Default")
      (node (ref "J3") (pin "6") (pinfunction "6_6") (pintype "passive"))
      (node (ref "U1") (pin "58") (pinfunction "PD11/FSMC_A16/USART3_CTS_58") (pintype "passive"))
    )
    (net (code "70") (name "/PD12") (class "Default")
      (node (ref "J3") (pin "7") (pinfunction "7_7") (pintype "passive"))
      (node (ref "U1") (pin "59") (pinfunction "PD12/FSMC_A17/TIM4_CH1_/__USART3_RTS_59") (pintype "passive"))
    )
    (net (code "71") (name "/PD13") (class "Default")
      (node (ref "J3") (pin "8") (pinfunction "8_8") (pintype "passive"))
      (node (ref "U1") (pin "60") (pinfunction "PD13/FSMC_A18/TIM4_CH2_60") (pintype "passive"))
    )
    (net (code "72") (name "/PD14") (class "Default")
      (node (ref "J3") (pin "9") (pinfunction "9_9") (pintype "passive"))
      (node (ref "U1") (pin "61") (pinfunction "PD14/FSMC_D0/TIM4_CH3_61") (pintype "passive"))
    )
    (net (code "73") (name "/PD15") (class "Default")
      (node (ref "J3") (pin "10") (pinfunction "10_10") (pintype "passive"))
      (node (ref "U1") (pin "62") (pinfunction "PD15/FSMC_D1/TIM4_CH4_62") (pintype "passive"))
    )
    (net (code "74") (name "/PE0") (class "Default")
      (node (ref "J3") (pin "41") (pinfunction "41_41") (pintype "passive"))
      (node (ref "U1") (pin "97") (pinfunction "PE0/TIM4_ETR_/_FSMC_NBL0_/__DCMI_D2_97") (pintype "passive"))
    )
    (net (code "75") (name "/PE1") (class "Default")
      (node (ref "J3") (pin "42") (pinfunction "42_42") (pintype "passive"))
      (node (ref "U1") (pin "98") (pinfunction "PE1/FSMC_NBL1_/_DCMI_D3_98") (pintype "passive"))
    )
    (net (code "76") (name "/PE2") (class "Default")
      (node (ref "J2") (pin "3") (pinfunction "3_3") (pintype "passive"))
      (node (ref "U1") (pin "1") (pinfunction "PE2/TRACECLK/_FSMC_A23_/__ETH_MII_TXD3_1") (pintype "passive"))
    )
    (net (code "77") (name "/PE5") (class "Default")
      (node (ref "J2") (pin "6") (pinfunction "6_6") (pintype "passive"))
      (node (ref "U1") (pin "4") (pinfunction "PE5/TRACED2_/_FSMC_A21_/__TIM9_CH1_/_DCMI_D6_4") (pintype "passive"))
    )
    (net (code "78") (name "/PE6") (class "Default")
      (node (ref "J2") (pin "7") (pinfunction "7_7") (pintype "passive"))
      (node (ref "U1") (pin "5") (pinfunction "PE6/TRACED3_/_FSMC_A22_/__TIM9_CH2_/_DCMI_D7_5") (pintype "passive"))
    )
    (net (code "79") (name "/PE7") (class "Default")
      (node (ref "J2") (pin "28") (pinfunction "28_28") (pintype "passive"))
      (node (ref "U1") (pin "38") (pinfunction "PE7/FSMC_D4/TIM1_ETR_38") (pintype "passive"))
    )
    (net (code "80") (name "/PE8") (class "Default")
      (node (ref "J2") (pin "29") (pinfunction "29_29") (pintype "passive"))
      (node (ref "U1") (pin "39") (pinfunction "PE8/FSMC_D5/TIM1_CH1N_39") (pintype "passive"))
    )
    (net (code "81") (name "/PE9") (class "Default")
      (node (ref "J2") (pin "30") (pinfunction "30_30") (pintype "passive"))
      (node (ref "U1") (pin "40") (pinfunction "PE9/FSMC_D6/TIM1_CH1_40") (pintype "passive"))
    )
    (net (code "82") (name "/PE10") (class "Default")
      (node (ref "J2") (pin "31") (pinfunction "31_31") (pintype "passive"))
      (node (ref "U1") (pin "41") (pinfunction "PE10/FSMC_D7/TIM1_CH2N_41") (pintype "passive"))
    )
    (net (code "83") (name "/PE12") (class "Default")
      (node (ref "J2") (pin "33") (pinfunction "33_33") (pintype "passive"))
      (node (ref "U1") (pin "43") (pinfunction "PE12/FSMC_D9/TIM1_CH3N_43") (pintype "passive"))
    )
    (net (code "84") (name "/PE15") (class "Default")
      (node (ref "J2") (pin "36") (pinfunction "36_36") (pintype "passive"))
      (node (ref "U1") (pin "46") (pinfunction "PE15/FSMC_D12/TIM1_BKIN_46") (pintype "passive"))
    )
    (net (code "85") (name "/VCC5V") (class "Default")
      (node (ref "C14") (pin "1") (pintype "passive"))
      (node (ref "J10") (pin "1") (pinfunction "1_1") (pintype "passive"))
      (node (ref "J2") (pin "43") (pinfunction "43_43") (pintype "passive"))
      (node (ref "J2") (pin "44") (pinfunction "44_44") (pintype "passive"))
      (node (ref "R10") (pin "2") (pinfunction "2_2") (pintype "passive"))
      (node (ref "R16") (pin "1") (pinfunction "1_1") (pintype "passive"))
      (node (ref "U3") (pin "1") (pinfunction "Vin_1") (pintype "passive"))
      (node (ref "U3") (pin "3") (pinfunction "EN_3") (pintype "passive"))
      (node (ref "USB1") (pin "A9") (pinfunction "VBUS_A9") (pintype "passive"))
      (node (ref "USB1") (pin "B9") (pinfunction "VBUS_B9") (pintype "passive"))
    )
    (net (code "86") (name "GND") (class "Default")
      (node (ref "C1") (pin "2") (pintype "passive"))
      (node (ref "C10") (pin "1") (pintype "passive"))
      (node (ref "C11") (pin "1") (pintype "passive"))
      (node (ref "C12") (pin "1") (pintype "passive"))
      (node (ref "C13") (pin "2") (pintype "passive"))
      (node (ref "C14") (pin "2") (pintype "passive"))
      (node (ref "C2") (pin "1") (pintype "passive"))
      (node (ref "C3") (pin "1") (pintype "passive"))
      (node (ref "C4") (pin "2") (pintype "passive"))
      (node (ref "C5") (pin "2") (pintype "passive"))
      (node (ref "C6") (pin "2") (pintype "passive"))
      (node (ref "C7") (pin "2") (pintype "passive"))
      (node (ref "C8") (pin "1") (pintype "passive"))
      (node (ref "C9") (pin "2") (pintype "passive"))
      (node (ref "E1") (pin "2") (pinfunction "2_2") (pintype "passive"))
      (node (ref "G1") (pin "2") (pinfunction "NC_2") (pintype "passive"))
      (node (ref "G1") (pin "4") (pinfunction "NC_4") (pintype "passive"))
      (node (ref "J1") (pin "8") (pinfunction "8_8") (pintype "passive"))
      (node (ref "J2") (pin "1") (pinfunction "1_1") (pintype "passive"))
      (node (ref "J2") (pin "2") (pinfunction "2_2") (pintype "passive"))
      (node (ref "J3") (pin "43") (pinfunction "43_43") (pintype "passive"))
      (node (ref "J3") (pin "44") (pinfunction "44_44") (pintype "passive"))
      (node (ref "J8") (pin "1") (pinfunction "1_1") (pintype "passive"))
      (node (ref "J9") (pin "1") (pinfunction "1_1") (pintype "passive"))
      (node (ref "KEY1") (pin "2") (pinfunction "2_2") (pintype "passive"))
      (node (ref "KEY2") (pin "2") (pinfunction "2_2") (pintype "passive"))
      (node (ref "KEY3") (pin "2") (pinfunction "2_2") (pintype "passive"))
      (node (ref "KEY4") (pin "2") (pinfunction "2_2") (pintype "passive"))
      (node (ref "R1") (pin "2") (pinfunction "2_2") (pintype "passive"))
      (node (ref "R2") (pin "1") (pinfunction "1_1") (pintype "passive"))
      (node (ref "R5") (pin "1") (pinfunction "1_1") (pintype "passive"))
      (node (ref "R8") (pin "1") (pinfunction "1_1") (pintype "passive"))
      (node (ref "U1") (pin "10") (pinfunction "VSS_10") (pintype "passive"))
      (node (ref "U1") (pin "20") (pinfunction "VSSA_20") (pintype "passive"))
      (node (ref "U1") (pin "27") (pinfunction "VSS_27") (pintype "passive"))
      (node (ref "U1") (pin "74") (pinfunction "VSS_74") (pintype "passive"))
      (node (ref "U2") (pin "1") (pinfunction "GND_1") (pintype "passive"))
      (node (ref "U3") (pin "2") (pinfunction "GND_2") (pintype "passive"))
      (node (ref "USB1") (pin "7") (pinfunction "EH_7") (pintype "passive"))
      (node (ref "USB1") (pin "A12") (pinfunction "GND_A12") (pintype "passive"))
      (node (ref "USB1") (pin "B12") (pinfunction "GND_B12") (pintype "passive"))
    )
    (net (code "87") (name "Net-(C8-Pad2)") (class "Default")
      (node (ref "C8") (pin "2") (pintype "passive"))
      (node (ref "U1") (pin "73") (pinfunction "VCAP_73") (pintype "passive"))
    )
    (net (code "88") (name "Net-(C10-Pad2)") (class "Default")
      (node (ref "C10") (pin "2") (pintype "passive"))
      (node (ref "U1") (pin "49") (pinfunction "VCAP_49") (pintype "passive"))
    )
    (net (code "89") (name "Net-(E1-Pad1)") (class "Default")
      (node (ref "E1") (pin "1") (pinfunction "1_1") (pintype "passive"))
      (node (ref "R10") (pin "1") (pinfunction "1_1") (pintype "passive"))
    )
    (net (code "90") (name "Net-(E2-Pad1)") (class "Default")
      (node (ref "E2") (pin "1") (pinfunction "1_1") (pintype "passive"))
      (node (ref "R12") (pin "1") (pinfunction "1_1") (pintype "passive"))
    )
    (net (code "91") (name "Net-(E2-Pad2)") (class "Default")
      (node (ref "E2") (pin "2") (pinfunction "2_2") (pintype "passive"))
      (node (ref "R19") (pin "2") (pinfunction "2_2") (pintype "passive"))
    )
    (net (code "92") (name "Net-(E3-Pad1)") (class "Default")
      (node (ref "E3") (pin "1") (pinfunction "1_1") (pintype "passive"))
      (node (ref "R13") (pin "1") (pinfunction "1_1") (pintype "passive"))
    )
    (net (code "93") (name "Net-(E3-Pad2)") (class "Default")
      (node (ref "E3") (pin "2") (pinfunction "2_2") (pintype "passive"))
      (node (ref "R20") (pin "2") (pinfunction "2_2") (pintype "passive"))
    )
    (net (code "94") (name "Net-(J1-Pad1)") (class "Default")
      (node (ref "J1") (pin "1") (pinfunction "1_1") (pintype "passive"))
      (node (ref "R14") (pin "2") (pinfunction "2_2") (pintype "passive"))
    )
    (net (code "95") (name "Net-(J1-Pad2)") (class "Default")
      (node (ref "J1") (pin "2") (pinfunction "2_2") (pintype "passive"))
      (node (ref "R9") (pin "1") (pinfunction "1_1") (pintype "passive"))
    )
    (net (code "96") (name "Net-(J1-Pad3)") (class "Default")
      (node (ref "J1") (pin "3") (pinfunction "3_3") (pintype "passive"))
      (node (ref "R15") (pin "2") (pinfunction "2_2") (pintype "passive"))
    )
    (net (code "97") (name "Net-(J1-Pad5)") (class "Default")
      (node (ref "J1") (pin "5") (pinfunction "5_5") (pintype "passive"))
      (node (ref "R16") (pin "2") (pinfunction "2_2") (pintype "passive"))
    )
    (net (code "98") (name "Net-(J1-Pad7)") (class "Default")
      (node (ref "J1") (pin "7") (pinfunction "7_7") (pintype "passive"))
      (node (ref "R17") (pin "2") (pinfunction "2_2") (pintype "passive"))
    )
    (net (code "99") (name "Net-(J1-Pad9)") (class "Default")
      (node (ref "J1") (pin "9") (pinfunction "9_9") (pintype "passive"))
      (node (ref "R25") (pin "2") (pinfunction "2_2") (pintype "passive"))
    )
    (net (code "100") (name "Net-(J1-Pad10)") (class "Default")
      (node (ref "J1") (pin "10") (pinfunction "10_10") (pintype "passive"))
      (node (ref "R26") (pin "1") (pinfunction "1_1") (pintype "passive"))
    )
    (net (code "101") (name "Net-(KEY1-Pad1)") (class "Default")
      (node (ref "KEY1") (pin "1") (pinfunction "1_1") (pintype "passive"))
      (node (ref "R11") (pin "1") (pinfunction "1_1") (pintype "passive"))
      (node (ref "R21") (pin "2") (pinfunction "2_2") (pintype "passive"))
    )
    (net (code "102") (name "Net-(KEY3-Pad1)") (class "Default")
      (node (ref "KEY3") (pin "1") (pinfunction "1_1") (pintype "passive"))
      (node (ref "R18") (pin "1") (pinfunction "1_1") (pintype "passive"))
      (node (ref "R22") (pin "2") (pinfunction "2_2") (pintype "passive"))
    )
    (net (code "103") (name "Net-(KEY4-Pad1)") (class "Default")
      (node (ref "KEY4") (pin "1") (pinfunction "1_1") (pintype "passive"))
      (node (ref "R23") (pin "2") (pinfunction "2_2") (pintype "passive"))
      (node (ref "R24") (pin "1") (pinfunction "1_1") (pintype "passive"))
    )
    (net (code "104") (name "Net-(U1-RFU)") (class "Default")
      (node (ref "R1") (pin "1") (pinfunction "1_1") (pintype "passive"))
      (node (ref "U1") (pin "99") (pinfunction "RFU_99") (pintype "passive"))
    )
    (net (code "105") (name "Net-(U1-VDD_12)") (class "Default")
      (node (ref "R2") (pin "2") (pinfunction "2_2") (pintype "passive"))
      (node (ref "R3") (pin "2") (pinfunction "2_2") (pintype "passive"))
      (node (ref "U1") (pin "19") (pinfunction "VDD_12_19") (pintype "passive"))
    )
    (net (code "106") (name "VCC3.3") (class "Default")
      (node (ref "C1") (pin "1") (pintype "passive"))
      (node (ref "C13") (pin "1") (pintype "passive"))
      (node (ref "C2") (pin "2") (pintype "passive"))
      (node (ref "C3") (pin "2") (pintype "passive"))
      (node (ref "C4") (pin "1") (pintype "passive"))
      (node (ref "C5") (pin "1") (pintype "passive"))
      (node (ref "C6") (pin "1") (pintype "passive"))
      (node (ref "C7") (pin "1") (pintype "passive"))
      (node (ref "C9") (pin "1") (pintype "passive"))
      (node (ref "J11") (pin "1") (pinfunction "1_1") (pintype "passive"))
      (node (ref "J3") (pin "1") (pinfunction "1_1") (pintype "passive"))
      (node (ref "J3") (pin "2") (pinfunction "2_2") (pintype "passive"))
      (node (ref "R11") (pin "2") (pinfunction "2_2") (pintype "passive"))
      (node (ref "R12") (pin "2") (pinfunction "2_2") (pintype "passive"))
      (node (ref "R13") (pin "2") (pinfunction "2_2") (pintype "passive"))
      (node (ref "R18") (pin "2") (pinfunction "2_2") (pintype "passive"))
      (node (ref "R24") (pin "2") (pinfunction "2_2") (pintype "passive"))
      (node (ref "R3") (pin "1") (pinfunction "1_1") (pintype "passive"))
      (node (ref "R4") (pin "1") (pinfunction "1_1") (pintype "passive"))
      (node (ref "R7") (pin "1") (pinfunction "1_1") (pintype "passive"))
      (node (ref "R9") (pin "2") (pinfunction "2_2") (pintype "passive"))
      (node (ref "U1") (pin "100") (pinfunction "VDD3_100") (pintype "passive"))
      (node (ref "U1") (pin "11") (pinfunction "VDD_11") (pintype "passive"))
      (node (ref "U1") (pin "21") (pinfunction "Vref+_21") (pintype "passive"))
      (node (ref "U1") (pin "22") (pinfunction "VDDA_22") (pintype "passive"))
      (node (ref "U1") (pin "28") (pinfunction "VDD_28") (pintype "passive"))
      (node (ref "U1") (pin "50") (pinfunction "VDD_50") (pintype "passive"))
      (node (ref "U1") (pin "6") (pinfunction "Vbat_6") (pintype "passive"))
      (node (ref "U1") (pin "75") (pinfunction "VDD_75") (pintype "passive"))
      (node (ref "U2") (pin "3") (pinfunction "VCC_3") (pintype "passive"))
      (node (ref "U3") (pin "5") (pinfunction "Vout_5") (pintype "passive"))
    )
    (net (code "107") (name "unconnected-(U3-BYP-Pad4)") (class "Default")
      (node (ref "U3") (pin "4") (pinfunction "BYP_4") (pintype "passive"))
    )
    (net (code "108") (name "unconnected-(USB1-CC1-PadA5)") (class "Default")
      (node (ref "USB1") (pin "A5") (pinfunction "CC1_A5") (pintype "passive"))
    )
    (net (code "109") (name "unconnected-(USB1-CC2-PadB5)") (class "Default")
      (node (ref "USB1") (pin "B5") (pinfunction "CC2_B5") (pintype "passive"))
    )
  )
)
